# ProDoc_Mouth_Board_2025-04-16.net
KiCad netlist of a schematic drawn in EasyEDA Pro
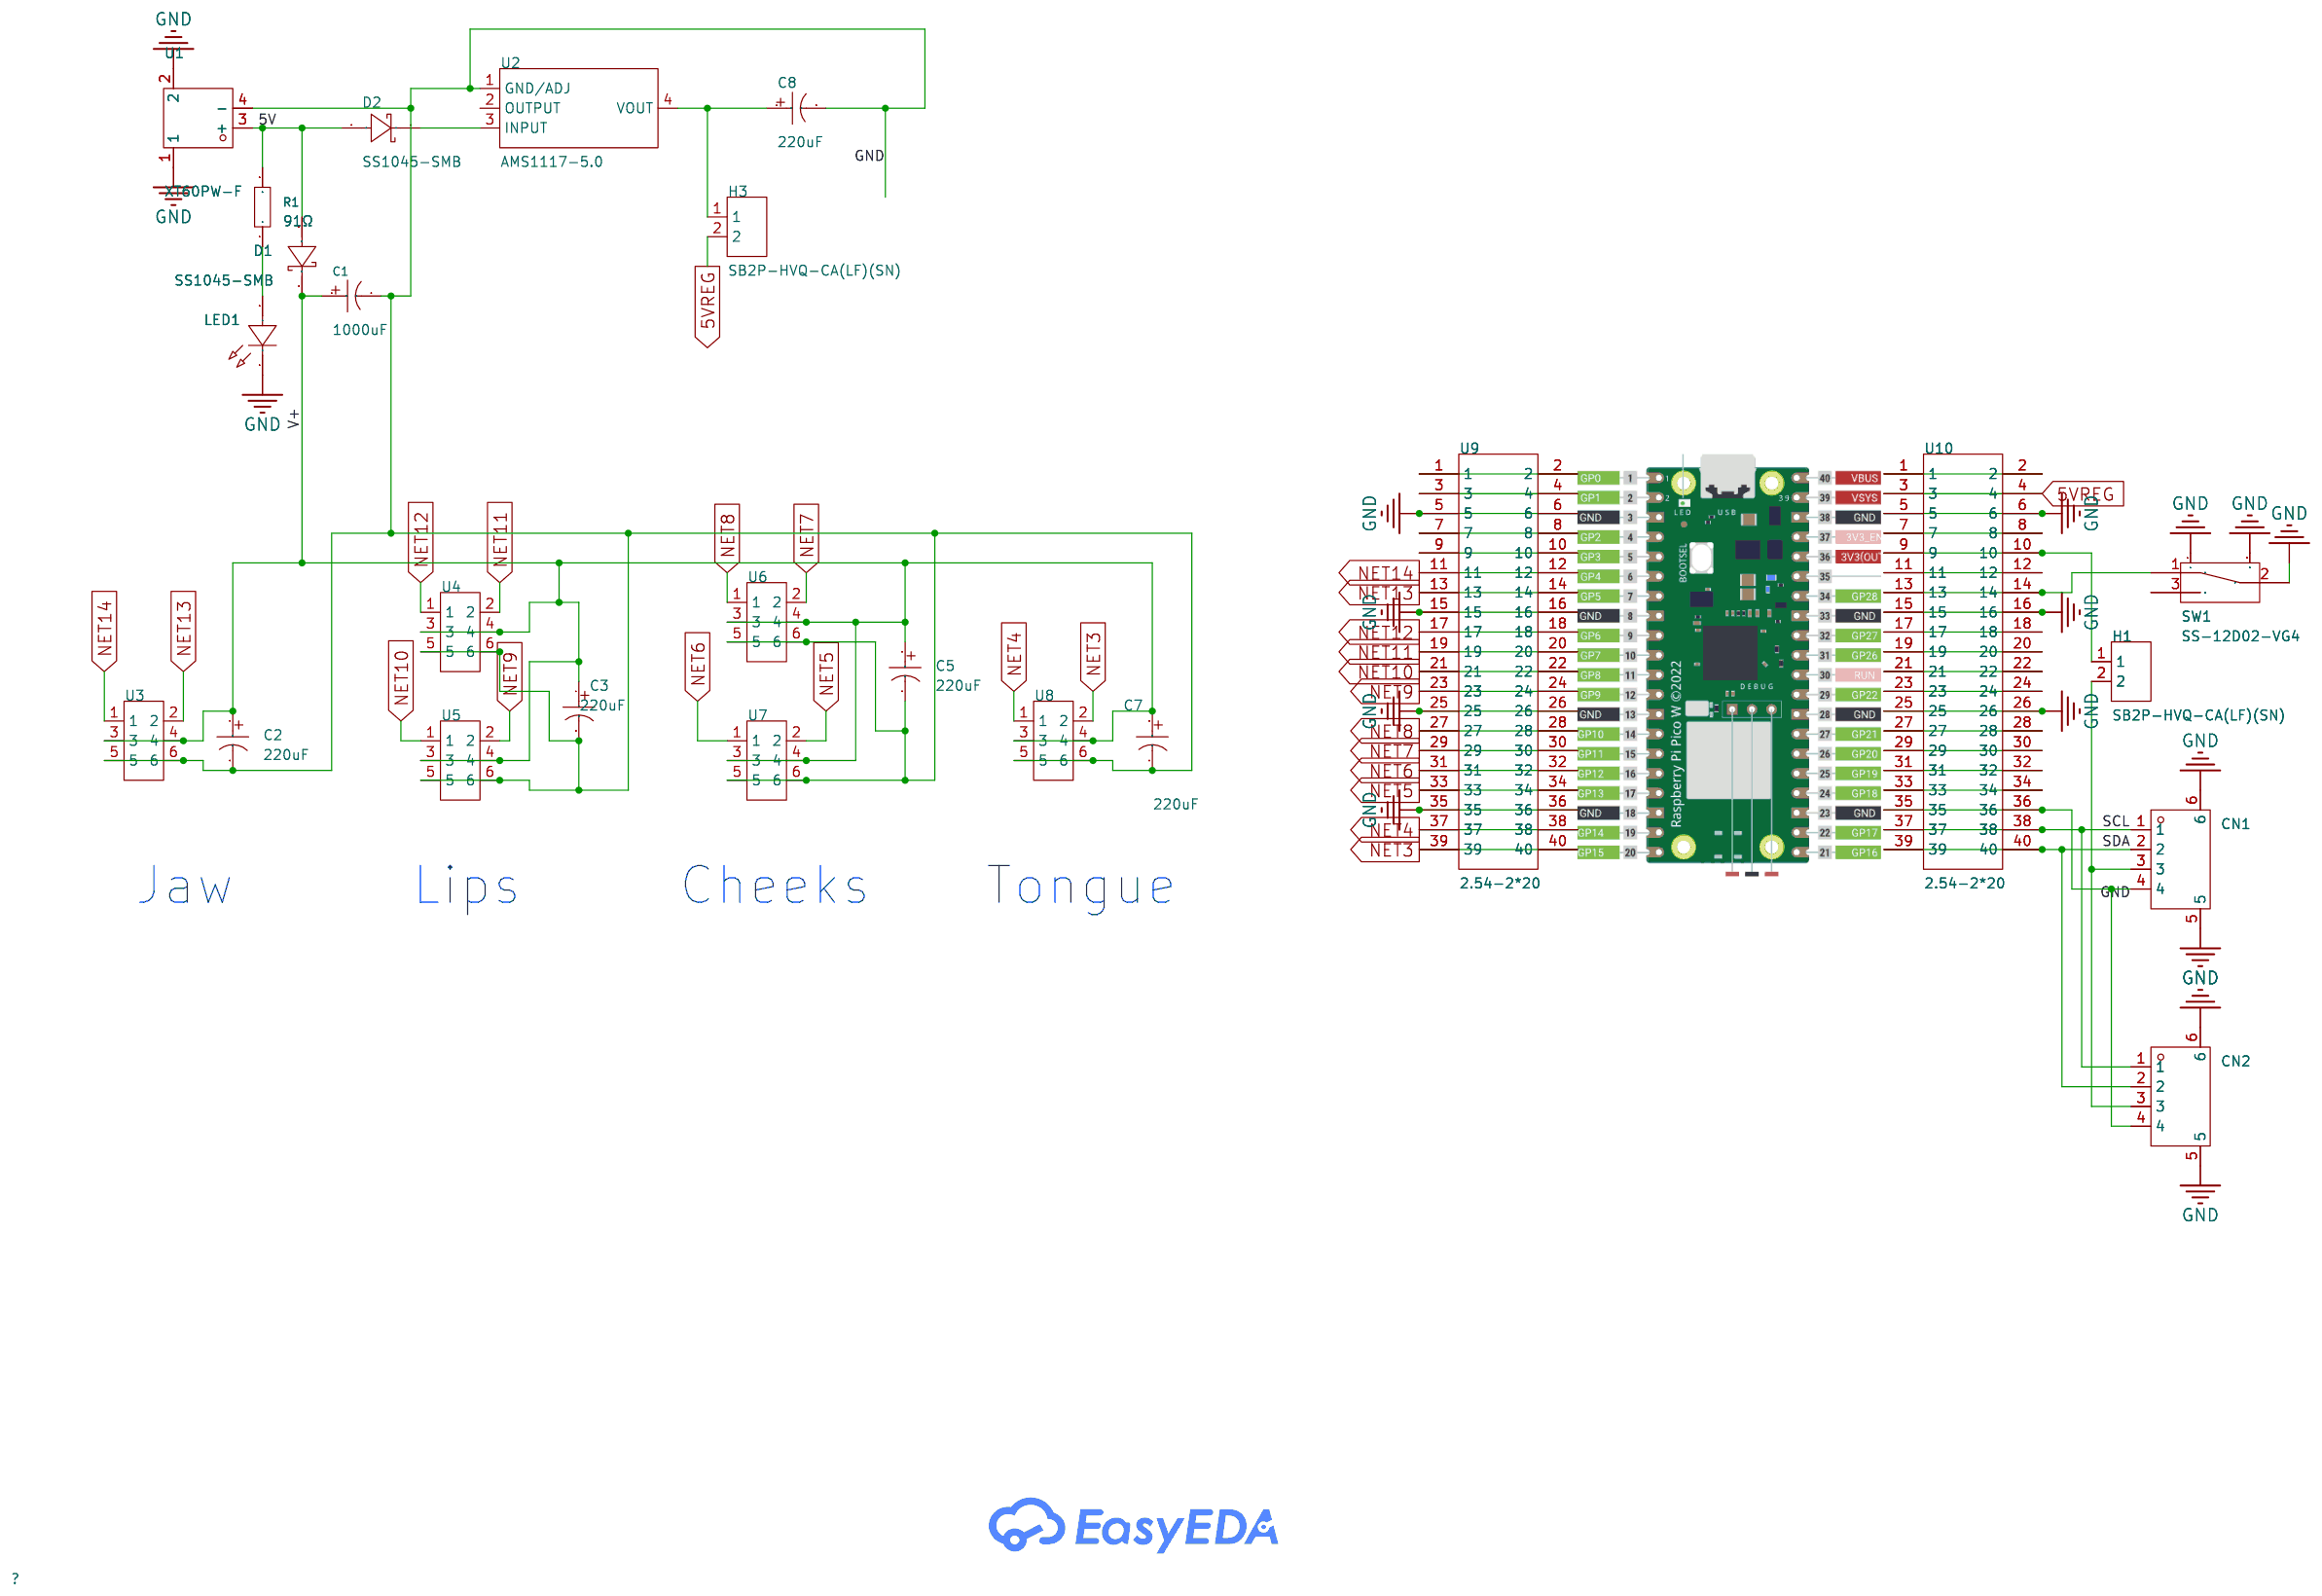
[diagram p0: schematic sheet]

(export (version "E")
  (design (tool "Eeschema 10.0.6"))
  (components
    (comp (ref "C1")
      (value "1000uF")
      (footprint "easyedapro:CAP-SMD_BD10.0-L10.3-W10.3-FD")
      (fields (field (name "Manufacturer Part") "RVT1C102M1010") (field (name "Manufacturer") "HONOR(荣誉)"))
      (libsource (lib "easyedapro") (part "RVT1C102M1010_C3359"))
    )
    (comp (ref "C2")
      (value "220uF")
      (footprint "easyedapro:CAP-SMD_BD6.3-L6.6-W6.6-FD")
      (fields (field (name "Manufacturer Part") "RVT1A221M0605") (field (name "Manufacturer") "ROQANG(容强)"))
      (libsource (lib "easyedapro") (part "RVT1A221M0605-C72494"))
    )
    (comp (ref "C3")
      (value "220uF")
      (footprint "easyedapro:CAP-SMD_BD6.3-L6.6-W6.6-FD")
      (fields (field (name "Manufacturer Part") "RVT1A221M0605") (field (name "Manufacturer") "ROQANG(容强)"))
      (libsource (lib "easyedapro") (part "RVT1A221M0605-C72494"))
    )
    (comp (ref "C5")
      (value "220uF")
      (footprint "easyedapro:CAP-SMD_BD6.3-L6.6-W6.6-FD")
      (fields (field (name "Manufacturer Part") "RVT1A221M0605") (field (name "Manufacturer") "ROQANG(容强)"))
      (libsource (lib "easyedapro") (part "RVT1A221M0605-C72494"))
    )
    (comp (ref "C7")
      (value "220uF")
      (footprint "easyedapro:CAP-SMD_BD6.3-L6.6-W6.6-FD")
      (fields (field (name "Manufacturer Part") "RVT1A221M0605") (field (name "Manufacturer") "ROQANG(容强)"))
      (libsource (lib "easyedapro") (part "RVT1A221M0605-C72494"))
    )
    (comp (ref "C8")
      (value "220uF")
      (footprint "easyedapro:CAP-SMD_BD6.3-L6.6-W6.6-FD")
      (fields (field (name "Manufacturer Part") "RVT1A221M0605") (field (name "Manufacturer") "ROQANG(容强)"))
      (libsource (lib "easyedapro") (part "RVT1A221M0605-C72494"))
    )
    (comp (ref "CN1")
      (value "HC-1.0-4PWT")
      (footprint "easyedapro:CONN-SMD_4P-P1.00_HCTL_HC-1.0-4PWT")
      (fields (field (name "Manufacturer") "HCTL(华灿天禄)"))
      (libsource (lib "easyedapro") (part "HC-1.0-4PWT"))
    )
    (comp (ref "CN2")
      (value "HC-1.0-4PWT")
      (footprint "easyedapro:CONN-SMD_4P-P1.00_HCTL_HC-1.0-4PWT")
      (fields (field (name "Manufacturer") "HCTL(华灿天禄)"))
      (libsource (lib "easyedapro") (part "HC-1.0-4PWT"))
    )
    (comp (ref "D1")
      (value "SS1045-SMB")
      (footprint "easyedapro:SMB_L4.4-W3.6-LS5.3-RD")
      (fields (field (name "Manufacturer") "GOODWORK(固得沃克)"))
      (libsource (lib "easyedapro") (part "SS1045-SMB"))
    )
    (comp (ref "D2")
      (value "SS1045-SMB")
      (footprint "easyedapro:SMB_L4.4-W3.6-LS5.3-RD")
      (fields (field (name "Manufacturer") "GOODWORK(固得沃克)"))
      (libsource (lib "easyedapro") (part "SS1045-SMB"))
    )
    (comp (ref "H1")
      (value "SB2P-HVQ-CA(LF)(SN)")
      (footprint "easyedapro:HDR-TH_2P-P2.54-V-M-1")
      (fields (field (name "Manufacturer") "JST"))
      (libsource (lib "easyedapro") (part "SB2P-HVQ-CA (LF)(SN)"))
    )
    (comp (ref "H3")
      (value "SB2P-HVQ-CA(LF)(SN)")
      (footprint "easyedapro:HDR-TH_2P-P2.54-V-M-1")
      (fields (field (name "Manufacturer") "JST"))
      (libsource (lib "easyedapro") (part "SB2P-HVQ-CA (LF)(SN)"))
    )
    (comp (ref "LED1")
      (value "XL-1608UBC-04")
      (footprint "easyedapro:LED0603-RD_BLUE")
      (fields (field (name "Manufacturer") "XINGLIGHT(成兴光)"))
      (libsource (lib "easyedapro") (part "XL-1608UBC-04"))
    )
    (comp (ref "R1")
      (value "91Ω")
      (footprint "easyedapro:R1206")
      (fields
        (field (name "Manufacturer Part") "1206W4F910JT5E")
        (field (name "Manufacturer") "UNI-ROYAL(厚声)")
      )
      (libsource (lib "easyedapro") (part "1206W4F910JT5E"))
    )
    (comp (ref "SW1")
      (value "SS-12D02-VG4")
      (footprint "easyedapro:SW-TH_SS-12D02-VG4")
      (fields (field (name "Manufacturer") "韩国韩荣"))
      (libsource (lib "easyedapro") (part "SS-12D02-VG4"))
    )
    (comp (ref "U1")
      (value "XT60PW-F")
      (footprint "easyedapro:TH_2P-XT60PW-F")
      (fields (field (name "Manufacturer") "AMASS(艾迈斯)"))
      (libsource (lib "easyedapro") (part "XT60PW-F_C428722"))
    )
    (comp (ref "U2")
      (value "AMS1117-5.0")
      (footprint "easyedapro:SOT-223-3_L6.5-W3.4-P2.30-LS7.0-BR")
      (fields (field (name "Manufacturer") "TECH PUBLIC(台舟)"))
      (libsource (lib "easyedapro") (part "AMS1117-5.0_C18212701"))
    )
    (comp (ref "U3")
      (value "ZX-PZ2.54-2-3PZZ")
      (footprint "easyedapro:HDR-TH_6P-P2.54-V-M-R2-C3-S2.54-1")
      (fields (field (name "Manufacturer") "Megastar(兆星)"))
      (libsource (lib "easyedapro") (part "ZX-PZ2.54-2-3PZZ"))
    )
    (comp (ref "U4")
      (value "ZX-PZ2.54-2-3PZZ")
      (footprint "easyedapro:HDR-TH_6P-P2.54-V-M-R2-C3-S2.54-1")
      (fields (field (name "Manufacturer") "Megastar(兆星)"))
      (libsource (lib "easyedapro") (part "ZX-PZ2.54-2-3PZZ"))
    )
    (comp (ref "U5")
      (value "ZX-PZ2.54-2-3PZZ")
      (footprint "easyedapro:HDR-TH_6P-P2.54-V-M-R2-C3-S2.54-1")
      (fields (field (name "Manufacturer") "Megastar(兆星)"))
      (libsource (lib "easyedapro") (part "ZX-PZ2.54-2-3PZZ"))
    )
    (comp (ref "U6")
      (value "ZX-PZ2.54-2-3PZZ")
      (footprint "easyedapro:HDR-TH_6P-P2.54-V-M-R2-C3-S2.54-1")
      (fields (field (name "Manufacturer") "Megastar(兆星)"))
      (libsource (lib "easyedapro") (part "ZX-PZ2.54-2-3PZZ"))
    )
    (comp (ref "U7")
      (value "ZX-PZ2.54-2-3PZZ")
      (footprint "easyedapro:HDR-TH_6P-P2.54-V-M-R2-C3-S2.54-1")
      (fields (field (name "Manufacturer") "Megastar(兆星)"))
      (libsource (lib "easyedapro") (part "ZX-PZ2.54-2-3PZZ"))
    )
    (comp (ref "U8")
      (value "ZX-PZ2.54-2-3PZZ")
      (footprint "easyedapro:HDR-TH_6P-P2.54-V-M-R2-C3-S2.54-1")
      (fields (field (name "Manufacturer") "Megastar(兆星)"))
      (libsource (lib "easyedapro") (part "ZX-PZ2.54-2-3PZZ"))
    )
    (comp (ref "U9")
      (value "2.54-2*20")
      (footprint "easyedapro:HDR-TH_40P-P2.54-V-F-R2-C20-S2.54")
      (fields (field (name "Manufacturer") "ZHOURI(洲日)"))
      (libsource (lib "easyedapro") (part "2.54-2*20"))
    )
    (comp (ref "U10")
      (value "2.54-2*20")
      (footprint "easyedapro:HDR-TH_40P-P2.54-V-F-R2-C20-S2.54")
      (fields (field (name "Manufacturer") "ZHOURI(洲日)"))
      (libsource (lib "easyedapro") (part "2.54-2*20"))
    )
  )
  (nets
    (net (code "1") (name "/5V") (class "Default")
      (node (ref "D1") (pin "2") (pinfunction "2_2") (pintype "unspecified"))
      (node (ref "D2") (pin "2") (pinfunction "2_2") (pintype "unspecified"))
      (node (ref "R1") (pin "2") (pinfunction "2_2") (pintype "input"))
      (node (ref "U1") (pin "3") (pinfunction "+_3") (pintype "unspecified"))
    )
    (net (code "2") (name "/SCL") (class "Default")
      (node (ref "CN1") (pin "1") (pinfunction "1_1") (pintype "unspecified"))
      (node (ref "CN2") (pin "1") (pinfunction "1_1") (pintype "unspecified"))
      (node (ref "U10") (pin "37") (pinfunction "37_37") (pintype "unspecified"))
      (node (ref "U10") (pin "38") (pinfunction "38_38") (pintype "unspecified"))
    )
    (net (code "3") (name "/SDA") (class "Default")
      (node (ref "CN1") (pin "2") (pinfunction "2_2") (pintype "unspecified"))
      (node (ref "CN2") (pin "2") (pinfunction "2_2") (pintype "unspecified"))
      (node (ref "U10") (pin "39") (pinfunction "39_39") (pintype "unspecified"))
      (node (ref "U10") (pin "40") (pinfunction "40_40") (pintype "unspecified"))
    )
    (net (code "4") (name "/V+") (class "Default")
      (node (ref "C1") (pin "1") (pinfunction "1_1") (pintype "input"))
      (node (ref "C2") (pin "1") (pinfunction "1_1") (pintype "input"))
      (node (ref "C3") (pin "1") (pinfunction "1_1") (pintype "input"))
      (node (ref "C5") (pin "1") (pinfunction "1_1") (pintype "input"))
      (node (ref "C7") (pin "1") (pinfunction "1_1") (pintype "input"))
      (node (ref "D1") (pin "1") (pinfunction "1_1") (pintype "unspecified"))
      (node (ref "U3") (pin "3") (pinfunction "3_3") (pintype "unspecified"))
      (node (ref "U3") (pin "4") (pinfunction "4_4") (pintype "unspecified"))
      (node (ref "U4") (pin "3") (pinfunction "3_3") (pintype "unspecified"))
      (node (ref "U4") (pin "4") (pinfunction "4_4") (pintype "unspecified"))
      (node (ref "U5") (pin "3") (pinfunction "3_3") (pintype "unspecified"))
      (node (ref "U5") (pin "4") (pinfunction "4_4") (pintype "unspecified"))
      (node (ref "U6") (pin "3") (pinfunction "3_3") (pintype "unspecified"))
      (node (ref "U6") (pin "4") (pinfunction "4_4") (pintype "unspecified"))
      (node (ref "U7") (pin "3") (pinfunction "3_3") (pintype "unspecified"))
      (node (ref "U7") (pin "4") (pinfunction "4_4") (pintype "unspecified"))
      (node (ref "U8") (pin "3") (pinfunction "3_3") (pintype "unspecified"))
      (node (ref "U8") (pin "4") (pinfunction "4_4") (pintype "unspecified"))
    )
    (net (code "5") (name "5VREG") (class "Default")
      (node (ref "H3") (pin "2") (pinfunction "2_2") (pintype "unspecified"))
      (node (ref "U10") (pin "3") (pinfunction "3_3") (pintype "unspecified"))
      (node (ref "U10") (pin "4") (pinfunction "4_4") (pintype "unspecified"))
    )
    (net (code "6") (name "GND") (class "Default")
      (node (ref "C1") (pin "2") (pinfunction "2_2") (pintype "input"))
      (node (ref "C2") (pin "2") (pinfunction "2_2") (pintype "input"))
      (node (ref "C3") (pin "2") (pinfunction "2_2") (pintype "input"))
      (node (ref "C5") (pin "2") (pinfunction "2_2") (pintype "input"))
      (node (ref "C7") (pin "2") (pinfunction "2_2") (pintype "input"))
      (node (ref "C8") (pin "2") (pinfunction "2_2") (pintype "input"))
      (node (ref "CN1") (pin "4") (pinfunction "4_4") (pintype "unspecified"))
      (node (ref "CN1") (pin "5") (pinfunction "5_5") (pintype "unspecified"))
      (node (ref "CN1") (pin "6") (pinfunction "6_6") (pintype "unspecified"))
      (node (ref "CN2") (pin "4") (pinfunction "4_4") (pintype "unspecified"))
      (node (ref "CN2") (pin "5") (pinfunction "5_5") (pintype "unspecified"))
      (node (ref "CN2") (pin "6") (pinfunction "6_6") (pintype "unspecified"))
      (node (ref "LED1") (pin "1") (pinfunction "K_1") (pintype "unspecified"))
      (node (ref "SW1") (pin "2") (pinfunction "2_2") (pintype "unspecified"))
      (node (ref "SW1") (pin "4") (pinfunction "4_4") (pintype "unspecified"))
      (node (ref "SW1") (pin "5") (pinfunction "5_5") (pintype "unspecified"))
      (node (ref "U1") (pin "1") (pinfunction "1_1") (pintype "unspecified"))
      (node (ref "U1") (pin "2") (pinfunction "2_2") (pintype "unspecified"))
      (node (ref "U1") (pin "4") (pinfunction "-_4") (pintype "unspecified"))
      (node (ref "U10") (pin "15") (pinfunction "15_15") (pintype "unspecified"))
      (node (ref "U10") (pin "16") (pinfunction "16_16") (pintype "unspecified"))
      (node (ref "U10") (pin "25") (pinfunction "25_25") (pintype "unspecified"))
      (node (ref "U10") (pin "26") (pinfunction "26_26") (pintype "unspecified"))
      (node (ref "U10") (pin "35") (pinfunction "35_35") (pintype "unspecified"))
      (node (ref "U10") (pin "36") (pinfunction "36_36") (pintype "unspecified"))
      (node (ref "U10") (pin "5") (pinfunction "5_5") (pintype "unspecified"))
      (node (ref "U10") (pin "6") (pinfunction "6_6") (pintype "unspecified"))
      (node (ref "U2") (pin "1") (pinfunction "GND/ADJ_1") (pintype "unspecified"))
      (node (ref "U3") (pin "5") (pinfunction "5_5") (pintype "unspecified"))
      (node (ref "U3") (pin "6") (pinfunction "6_6") (pintype "unspecified"))
      (node (ref "U4") (pin "5") (pinfunction "5_5") (pintype "unspecified"))
      (node (ref "U4") (pin "6") (pinfunction "6_6") (pintype "unspecified"))
      (node (ref "U5") (pin "5") (pinfunction "5_5") (pintype "unspecified"))
      (node (ref "U5") (pin "6") (pinfunction "6_6") (pintype "unspecified"))
      (node (ref "U6") (pin "5") (pinfunction "5_5") (pintype "unspecified"))
      (node (ref "U6") (pin "6") (pinfunction "6_6") (pintype "unspecified"))
      (node (ref "U7") (pin "5") (pinfunction "5_5") (pintype "unspecified"))
      (node (ref "U7") (pin "6") (pinfunction "6_6") (pintype "unspecified"))
      (node (ref "U8") (pin "5") (pinfunction "5_5") (pintype "unspecified"))
      (node (ref "U8") (pin "6") (pinfunction "6_6") (pintype "unspecified"))
      (node (ref "U9") (pin "15") (pinfunction "15_15") (pintype "unspecified"))
      (node (ref "U9") (pin "16") (pinfunction "16_16") (pintype "unspecified"))
      (node (ref "U9") (pin "25") (pinfunction "25_25") (pintype "unspecified"))
      (node (ref "U9") (pin "26") (pinfunction "26_26") (pintype "unspecified"))
      (node (ref "U9") (pin "35") (pinfunction "35_35") (pintype "unspecified"))
      (node (ref "U9") (pin "36") (pinfunction "36_36") (pintype "unspecified"))
      (node (ref "U9") (pin "5") (pinfunction "5_5") (pintype "unspecified"))
      (node (ref "U9") (pin "6") (pinfunction "6_6") (pintype "unspecified"))
    )
    (net (code "7") (name "NET3") (class "Default")
      (node (ref "U8") (pin "2") (pinfunction "2_2") (pintype "unspecified"))
      (node (ref "U9") (pin "39") (pinfunction "39_39") (pintype "unspecified"))
      (node (ref "U9") (pin "40") (pinfunction "40_40") (pintype "unspecified"))
    )
    (net (code "8") (name "NET4") (class "Default")
      (node (ref "U8") (pin "1") (pinfunction "1_1") (pintype "unspecified"))
      (node (ref "U9") (pin "37") (pinfunction "37_37") (pintype "unspecified"))
      (node (ref "U9") (pin "38") (pinfunction "38_38") (pintype "unspecified"))
    )
    (net (code "9") (name "NET5") (class "Default")
      (node (ref "U7") (pin "2") (pinfunction "2_2") (pintype "unspecified"))
      (node (ref "U9") (pin "33") (pinfunction "33_33") (pintype "unspecified"))
      (node (ref "U9") (pin "34") (pinfunction "34_34") (pintype "unspecified"))
    )
    (net (code "10") (name "NET6") (class "Default")
      (node (ref "U7") (pin "1") (pinfunction "1_1") (pintype "unspecified"))
      (node (ref "U9") (pin "31") (pinfunction "31_31") (pintype "unspecified"))
      (node (ref "U9") (pin "32") (pinfunction "32_32") (pintype "unspecified"))
    )
    (net (code "11") (name "NET7") (class "Default")
      (node (ref "U6") (pin "2") (pinfunction "2_2") (pintype "unspecified"))
      (node (ref "U9") (pin "29") (pinfunction "29_29") (pintype "unspecified"))
      (node (ref "U9") (pin "30") (pinfunction "30_30") (pintype "unspecified"))
    )
    (net (code "12") (name "NET8") (class "Default")
      (node (ref "U6") (pin "1") (pinfunction "1_1") (pintype "unspecified"))
      (node (ref "U9") (pin "27") (pinfunction "27_27") (pintype "unspecified"))
      (node (ref "U9") (pin "28") (pinfunction "28_28") (pintype "unspecified"))
    )
    (net (code "13") (name "NET9") (class "Default")
      (node (ref "U5") (pin "2") (pinfunction "2_2") (pintype "unspecified"))
      (node (ref "U9") (pin "23") (pinfunction "23_23") (pintype "unspecified"))
      (node (ref "U9") (pin "24") (pinfunction "24_24") (pintype "unspecified"))
    )
    (net (code "14") (name "NET10") (class "Default")
      (node (ref "U5") (pin "1") (pinfunction "1_1") (pintype "unspecified"))
      (node (ref "U9") (pin "21") (pinfunction "21_21") (pintype "unspecified"))
      (node (ref "U9") (pin "22") (pinfunction "22_22") (pintype "unspecified"))
    )
    (net (code "15") (name "NET11") (class "Default")
      (node (ref "U4") (pin "2") (pinfunction "2_2") (pintype "unspecified"))
      (node (ref "U9") (pin "19") (pinfunction "19_19") (pintype "unspecified"))
      (node (ref "U9") (pin "20") (pinfunction "20_20") (pintype "unspecified"))
    )
    (net (code "16") (name "NET12") (class "Default")
      (node (ref "U4") (pin "1") (pinfunction "1_1") (pintype "unspecified"))
      (node (ref "U9") (pin "17") (pinfunction "17_17") (pintype "unspecified"))
      (node (ref "U9") (pin "18") (pinfunction "18_18") (pintype "unspecified"))
    )
    (net (code "17") (name "NET13") (class "Default")
      (node (ref "U3") (pin "2") (pinfunction "2_2") (pintype "unspecified"))
      (node (ref "U9") (pin "13") (pinfunction "13_13") (pintype "unspecified"))
      (node (ref "U9") (pin "14") (pinfunction "14_14") (pintype "unspecified"))
    )
    (net (code "18") (name "NET14") (class "Default")
      (node (ref "U3") (pin "1") (pinfunction "1_1") (pintype "unspecified"))
      (node (ref "U9") (pin "11") (pinfunction "11_11") (pintype "unspecified"))
      (node (ref "U9") (pin "12") (pinfunction "12_12") (pintype "unspecified"))
    )
    (net (code "19") (name "Net-(CN1-Pad3)") (class "Default")
      (node (ref "CN1") (pin "3") (pinfunction "3_3") (pintype "unspecified"))
      (node (ref "CN2") (pin "3") (pinfunction "3_3") (pintype "unspecified"))
      (node (ref "H1") (pin "2") (pinfunction "2_2") (pintype "unspecified"))
    )
    (net (code "20") (name "Net-(H1-Pad1)") (class "Default")
      (node (ref "H1") (pin "1") (pinfunction "1_1") (pintype "unspecified"))
      (node (ref "U10") (pin "10") (pinfunction "10_10") (pintype "unspecified"))
      (node (ref "U10") (pin "9") (pinfunction "9_9") (pintype "unspecified"))
    )
    (net (code "21") (name "Net-(LED1-A)") (class "Default")
      (node (ref "LED1") (pin "2") (pinfunction "A_2") (pintype "unspecified"))
      (node (ref "R1") (pin "1") (pinfunction "1_1") (pintype "input"))
    )
    (net (code "22") (name "Net-(SW1-Pad1)") (class "Default")
      (node (ref "SW1") (pin "1") (pinfunction "1_1") (pintype "unspecified"))
      (node (ref "U10") (pin "13") (pinfunction "13_13") (pintype "unspecified"))
      (node (ref "U10") (pin "14") (pinfunction "14_14") (pintype "unspecified"))
    )
    (net (code "23") (name "Net-(U2-INPUT)") (class "Default")
      (node (ref "D2") (pin "1") (pinfunction "1_1") (pintype "unspecified"))
      (node (ref "U2") (pin "3") (pinfunction "INPUT_3") (pintype "unspecified"))
    )
    (net (code "24") (name "Net-(U2-VOUT)") (class "Default")
      (node (ref "C8") (pin "1") (pinfunction "1_1") (pintype "input"))
      (node (ref "H3") (pin "1") (pinfunction "1_1") (pintype "unspecified"))
      (node (ref "U2") (pin "4") (pinfunction "VOUT_4") (pintype "unspecified"))
    )
    (net (code "25") (name "Net-(U9-Pad1)") (class "Default")
      (node (ref "U9") (pin "1") (pinfunction "1_1") (pintype "unspecified"))
      (node (ref "U9") (pin "2") (pinfunction "2_2") (pintype "unspecified"))
    )
    (net (code "26") (name "Net-(U9-Pad3)") (class "Default")
      (node (ref "U9") (pin "3") (pinfunction "3_3") (pintype "unspecified"))
      (node (ref "U9") (pin "4") (pinfunction "4_4") (pintype "unspecified"))
    )
    (net (code "27") (name "Net-(U9-Pad7)") (class "Default")
      (node (ref "U9") (pin "7") (pinfunction "7_7") (pintype "unspecified"))
      (node (ref "U9") (pin "8") (pinfunction "8_8") (pintype "unspecified"))
    )
    (net (code "28") (name "Net-(U9-Pad10)") (class "Default")
      (node (ref "U9") (pin "10") (pinfunction "10_10") (pintype "unspecified"))
      (node (ref "U9") (pin "9") (pinfunction "9_9") (pintype "unspecified"))
    )
    (net (code "29") (name "Net-(U10-Pad1)") (class "Default")
      (node (ref "U10") (pin "1") (pinfunction "1_1") (pintype "unspecified"))
      (node (ref "U10") (pin "2") (pinfunction "2_2") (pintype "unspecified"))
    )
    (net (code "30") (name "Net-(U10-Pad7)") (class "Default")
      (node (ref "U10") (pin "7") (pinfunction "7_7") (pintype "unspecified"))
      (node (ref "U10") (pin "8") (pinfunction "8_8") (pintype "unspecified"))
    )
    (net (code "31") (name "Net-(U10-Pad11)") (class "Default")
      (node (ref "U10") (pin "11") (pinfunction "11_11") (pintype "unspecified"))
      (node (ref "U10") (pin "12") (pinfunction "12_12") (pintype "unspecified"))
    )
    (net (code "32") (name "Net-(U10-Pad17)") (class "Default")
      (node (ref "U10") (pin "17") (pinfunction "17_17") (pintype "unspecified"))
      (node (ref "U10") (pin "18") (pinfunction "18_18") (pintype "unspecified"))
    )
    (net (code "33") (name "Net-(U10-Pad19)") (class "Default")
      (node (ref "U10") (pin "19") (pinfunction "19_19") (pintype "unspecified"))
      (node (ref "U10") (pin "20") (pinfunction "20_20") (pintype "unspecified"))
    )
    (net (code "34") (name "Net-(U10-Pad21)") (class "Default")
      (node (ref "U10") (pin "21") (pinfunction "21_21") (pintype "unspecified"))
      (node (ref "U10") (pin "22") (pinfunction "22_22") (pintype "unspecified"))
    )
    (net (code "35") (name "Net-(U10-Pad23)") (class "Default")
      (node (ref "U10") (pin "23") (pinfunction "23_23") (pintype "unspecified"))
      (node (ref "U10") (pin "24") (pinfunction "24_24") (pintype "unspecified"))
    )
    (net (code "36") (name "Net-(U10-Pad27)") (class "Default")
      (node (ref "U10") (pin "27") (pinfunction "27_27") (pintype "unspecified"))
      (node (ref "U10") (pin "28") (pinfunction "28_28") (pintype "unspecified"))
    )
    (net (code "37") (name "Net-(U10-Pad29)") (class "Default")
      (node (ref "U10") (pin "29") (pinfunction "29_29") (pintype "unspecified"))
      (node (ref "U10") (pin "30") (pinfunction "30_30") (pintype "unspecified"))
    )
    (net (code "38") (name "Net-(U10-Pad31)") (class "Default")
      (node (ref "U10") (pin "31") (pinfunction "31_31") (pintype "unspecified"))
      (node (ref "U10") (pin "32") (pinfunction "32_32") (pintype "unspecified"))
    )
    (net (code "39") (name "Net-(U10-Pad33)") (class "Default")
      (node (ref "U10") (pin "33") (pinfunction "33_33") (pintype "unspecified"))
      (node (ref "U10") (pin "34") (pinfunction "34_34") (pintype "unspecified"))
    )
    (net (code "40") (name "unconnected-(SW1-Pad3)") (class "Default")
      (node (ref "SW1") (pin "3") (pinfunction "3_3") (pintype "unspecified"))
    )
    (net (code "41") (name "unconnected-(U2-OUTPUT-Pad2)") (class "Default")
      (node (ref "U2") (pin "2") (pinfunction "OUTPUT_2") (pintype "unspecified"))
    )
  )
)
